# MCU.net
KiCad netlist of a schematic drawn in Altium Designer
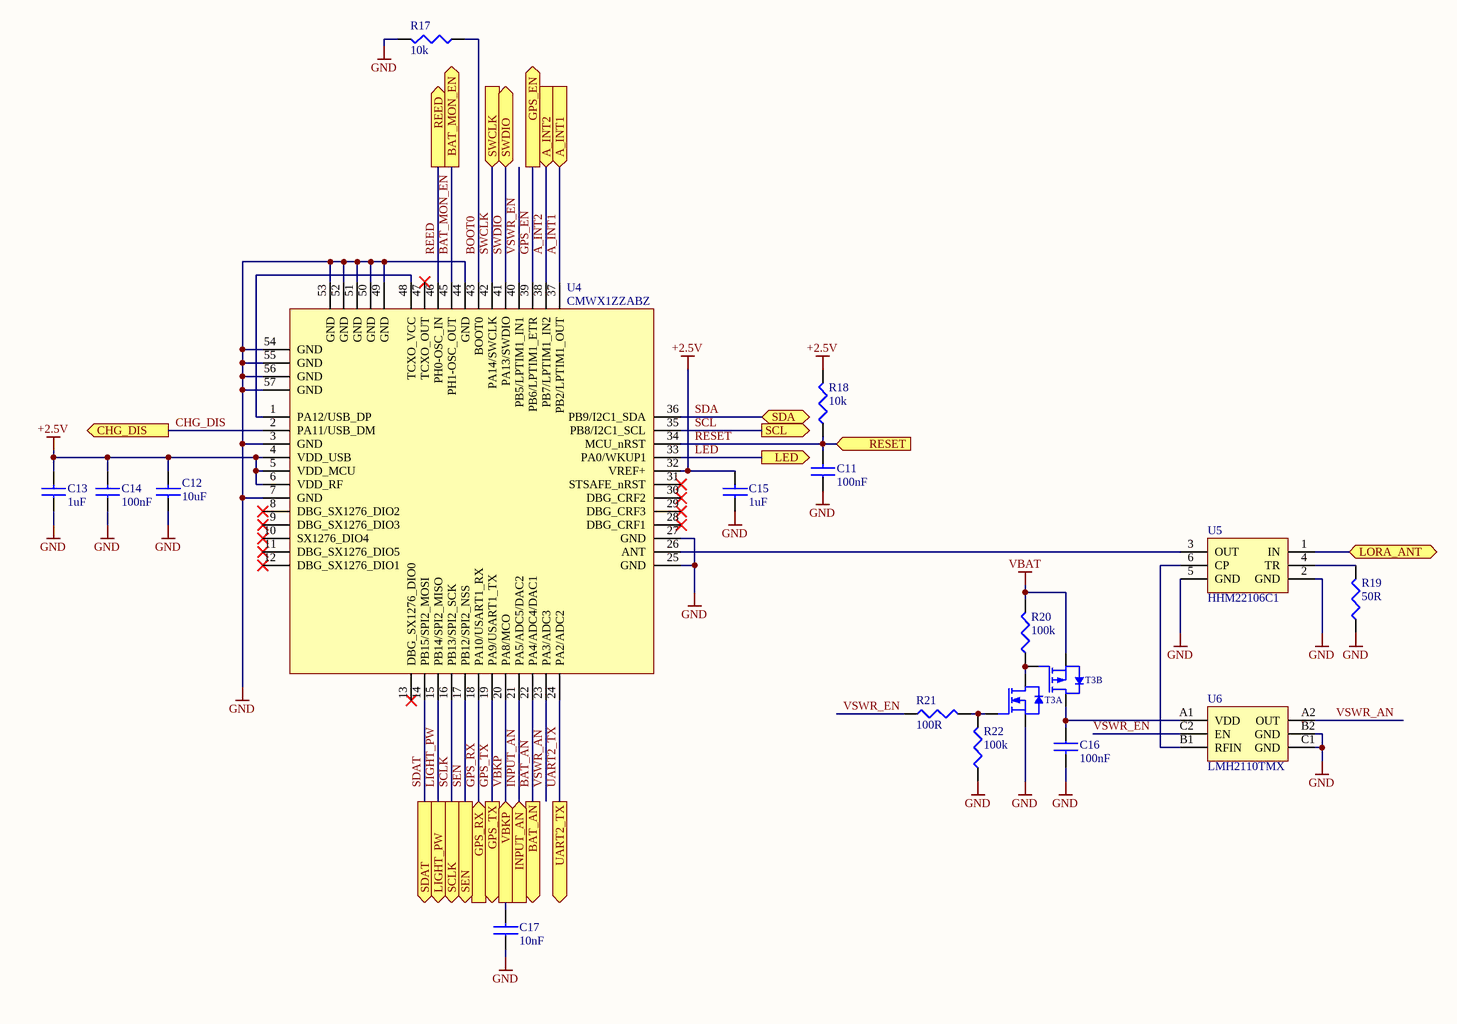
[diagram p0: MCU.SchDoc]

(export (version "E")
  (design (tool "Eeschema 10.0.6"))
  (components
    (comp (ref "C11")
      (value "100nF")
      (footprint "CAP0402")
      (fields
        (field (name "MANUFACTURER") "Multicomp")
        (field (name "MANUFACTURER PART NUMBER") "MC0402X104J160CT")
        (field (name "TOLERANCE") "5%")
      )
      (libsource (lib "Passive") (part "C - 100nF/0402"))
    )
    (comp (ref "C12")
      (value "10uF")
      (footprint "CAP0603")
      (description "10uf/0603/20%")
      (fields
        (field (name "MANUFACTURER") "KEMET")
        (field (name "MANUFACTURER PART NUMBER") "C0603C106M8PACTU")
      )
      (libsource (lib "pira-smart-schlib") (part "10uF"))
    )
    (comp (ref "C13")
      (value "1uF")
      (footprint "CAP0402")
      (description "CAP CER 1UF 10V 20% X5R 0402")
      (fields
        (field (name "MANUFACTURER") "Murata")
        (field (name "MANUFACTURER PART NUMBER") "GRM155R61A105ME15D")
      )
      (libsource (lib "Passive") (part "C - 1uF/0402"))
    )
    (comp (ref "C14")
      (value "100nF")
      (footprint "CAP0402")
      (fields
        (field (name "MANUFACTURER") "Multicomp")
        (field (name "MANUFACTURER PART NUMBER") "MC0402X104J160CT")
        (field (name "TOLERANCE") "5%")
      )
      (libsource (lib "Passive") (part "C - 100nF/0402"))
    )
    (comp (ref "C15")
      (value "1uF")
      (footprint "CAP0402")
      (description "CAP CER 1UF 10V 20% X5R 0402")
      (fields
        (field (name "MANUFACTURER") "Murata")
        (field (name "MANUFACTURER PART NUMBER") "GRM155R61A105ME15D")
      )
      (libsource (lib "Passive") (part "C - 1uF/0402"))
    )
    (comp (ref "C16")
      (value "100nF")
      (footprint "CAP0402")
      (fields
        (field (name "MANUFACTURER") "Multicomp")
        (field (name "MANUFACTURER PART NUMBER") "MC0402X104J160CT")
        (field (name "TOLERANCE") "5%")
      )
      (libsource (lib "Passive") (part "C - 100nF/0402"))
    )
    (comp (ref "C17")
      (value "10nF")
      (footprint "CAP0402")
      (description "CAP CER 10000PF 16V X7R 0402")
      (fields
        (field (name "MANUFACTURER") "Murata")
        (field (name "MANUFACTURER PART NUMBER") "GRM155R71C103KA01D")
      )
      (libsource (lib "Passive") (part "C - 10nF/0402"))
    )
    (comp (ref "R17")
      (value "10k")
      (footprint "RES0402")
      (fields
        (field (name "MANUFACTURER") "Multicomp")
        (field (name "MANUFACTURER PART NUMBER") "MCWR04X1002FTL")
        (field (name "TOLERANCE") "1%")
      )
      (libsource (lib "Passive") (part "R - 10k/0402"))
    )
    (comp (ref "R18")
      (value "10k")
      (footprint "RES0402")
      (fields
        (field (name "MANUFACTURER") "Multicomp")
        (field (name "MANUFACTURER PART NUMBER") "MCWR04X1002FTL")
        (field (name "TOLERANCE") "1%")
      )
      (libsource (lib "Passive") (part "R - 10k/0402"))
    )
    (comp (ref "R19")
      (value "50R")
      (footprint "RES0402")
      (description "SMD Chip Resistor, 0402 [1005 Metric], 50 ohm, FC Series, 30 V, Thin Film, 50 mW")
      (fields
        (field (name "MANUFACTURER") "Vishay")
        (field (name "MANUFACTURER PART NUMBER") "CRCW060351R0FKEA")
      )
      (libsource (lib "Passive") (part "R - 50R"))
    )
    (comp (ref "R20")
      (value "100k")
      (footprint "RES0402")
      (description "MULTICOMP   MCWR04X1003FTL   RES, THICK FILM, 100KOHM, 1%, 0.0625W")
      (fields
        (field (name "MANUFACTURER") "Multicomp")
        (field (name "MANUFACTURER PART NUMBER") "MCWR04X1003FTL")
      )
      (libsource (lib "Passive") (part "R - 100k/0402"))
    )
    (comp (ref "R21")
      (value "100R")
      (footprint "RES0402")
      (fields
        (field (name "MANUFACTURER") "Multicomp")
        (field (name "MANUFACTURER PART NUMBER") "MCMR04X1000FTL")
        (field (name "TOLERANCE") "1%")
      )
      (libsource (lib "Passive") (part "R - 100R/0402"))
    )
    (comp (ref "R22")
      (value "100k")
      (footprint "RES0402")
      (description "MULTICOMP   MCWR04X1003FTL   RES, THICK FILM, 100KOHM, 1%, 0.0625W")
      (fields
        (field (name "MANUFACTURER") "Multicomp")
        (field (name "MANUFACTURER PART NUMBER") "MCWR04X1003FTL")
      )
      (libsource (lib "Passive") (part "R - 100k/0402"))
    )
    (comp (ref "T3")
      (value "VT6M1T2CR")
      (footprint "VMT6")
      (description "Dual MOSFET, N and P Channel, 100 mA, 20 V, 2.5 ohm, 4.5 V, 1 V")
      (fields (field (name "AUTHOR") "Ciril Golob"))
      (libsource (lib "Active") (part "T_M - VT6M1T2CR"))
    )
    (comp (ref "U4")
      (value "CMWX1ZZABZ")
      (footprint "Lora Module ES0")
      (description "RF Module, FSK, OOK, LoRa, 4.8Kbps, 915MHz, -135.5dBm, 2.2V to 3.6V, I2C, SPI, UART, USB")
      (fields
        (field (name "MANUFACTURER") "Murata")
        (field (name "MANUFACTURER PART NUMBER") "CMWX1ZZABZ-091")
      )
      (libsource (lib "Active") (part "MCU - CMWX1ZZABZ"))
    )
    (comp (ref "U5")
      (value "HHM22106C1")
      (footprint "HHM22106C1")
      (description "Signal Conditioning DIRECTIONAL COUPLER 700-2700MHz")
      (fields (field (name "MANUFACTURER") "u-blox") (field (name "MANUFACTURER PART NUMBER") "MAX-M8Q-0"))
      (libsource (lib "Active") (part "RF - HHM22106C1"))
    )
    (comp (ref "U6")
      (value "LMH2110TMX")
      (footprint "DSBGA-6")
      (description "RF Detector IC GSM, EDGE, CDMA 50MHz ~ 8GHz -40dBm ~ 5dBm ±0,5dB")
      (fields (field (name "MANUFACTURER") "u-blox") (field (name "MANUFACTURER PART NUMBER") "MAX-M8Q-0"))
      (libsource (lib "Active") (part "RF - LMH2110TMX"))
    )
  )
  (nets
    (net (code "1") (name "+2.5V") (class "Default")
      (node (ref "C12") (pin "2") (pinfunction "2_2") (pintype "passive"))
      (node (ref "C13") (pin "2") (pinfunction "2_2") (pintype "passive"))
      (node (ref "C14") (pin "2") (pinfunction "2_2") (pintype "passive"))
      (node (ref "C15") (pin "2") (pinfunction "2_2") (pintype "passive"))
      (node (ref "R18") (pin "2") (pinfunction "2_2") (pintype "passive"))
      (node (ref "U4") (pin "32") (pinfunction "VREF+_32") (pintype "passive"))
      (node (ref "U4") (pin "4") (pinfunction "VDD_USB_4") (pintype "passive"))
      (node (ref "U4") (pin "5") (pinfunction "VDD_MCU_5") (pintype "passive"))
      (node (ref "U4") (pin "6") (pinfunction "VDD_RF_6") (pintype "passive"))
    )
    (net (code "2") (name "/A_INT1") (class "Default")
      (node (ref "U4") (pin "37") (pinfunction "PB2/LPTIM1_OUT_37") (pintype "passive"))
    )
    (net (code "3") (name "/A_INT2") (class "Default")
      (node (ref "U4") (pin "38") (pinfunction "PB7/LPTIM1_IN2_38") (pintype "passive"))
    )
    (net (code "4") (name "/BAT_AN") (class "Default")
      (node (ref "U4") (pin "22") (pinfunction "PA4/ADC4/DAC1_22") (pintype "passive"))
    )
    (net (code "5") (name "/BAT_MON_EN") (class "Default")
      (node (ref "U4") (pin "45") (pinfunction "PH1-OSC_OUT_45") (pintype "passive"))
    )
    (net (code "6") (name "/BOOT0") (class "Default")
      (node (ref "R17") (pin "1") (pinfunction "1_1") (pintype "passive"))
      (node (ref "U4") (pin "43") (pinfunction "BOOT0_43") (pintype "passive"))
    )
    (net (code "7") (name "/CHG_DIS") (class "Default")
      (node (ref "U4") (pin "2") (pinfunction "PA11/USB_DM_2") (pintype "passive"))
    )
    (net (code "8") (name "/GPS_EN") (class "Default")
      (node (ref "U4") (pin "39") (pinfunction "PB6/LPTIM1_ETR_39") (pintype "passive"))
    )
    (net (code "9") (name "/GPS_RX") (class "Default")
      (node (ref "U4") (pin "18") (pinfunction "PA10/USART1_RX_18") (pintype "passive"))
    )
    (net (code "10") (name "/GPS_TX") (class "Default")
      (node (ref "U4") (pin "19") (pinfunction "PA9/USART1_TX_19") (pintype "passive"))
    )
    (net (code "11") (name "/INPUT_AN") (class "Default")
      (node (ref "U4") (pin "21") (pinfunction "PA5/ADC5/DAC2_21") (pintype "passive"))
    )
    (net (code "12") (name "/LED") (class "Default")
      (node (ref "U4") (pin "33") (pinfunction "PA0/WKUP1_33") (pintype "passive"))
    )
    (net (code "13") (name "/LIGHT_PW") (class "Default")
      (node (ref "U4") (pin "15") (pinfunction "PB14/SPI2_MISO_15") (pintype "passive"))
    )
    (net (code "14") (name "/LORA_ANT") (class "Default")
      (node (ref "U5") (pin "1") (pinfunction "IN_1") (pintype "passive"))
    )
    (net (code "15") (name "/REED") (class "Default")
      (node (ref "U4") (pin "46") (pinfunction "PH0-OSC_IN_46") (pintype "passive"))
    )
    (net (code "16") (name "/RESET") (class "Default")
      (node (ref "C11") (pin "2") (pinfunction "2_2") (pintype "passive"))
      (node (ref "R18") (pin "1") (pinfunction "1_1") (pintype "passive"))
      (node (ref "U4") (pin "34") (pinfunction "MCU_nRST_34") (pintype "passive"))
    )
    (net (code "17") (name "/SCL") (class "Default")
      (node (ref "U4") (pin "35") (pinfunction "PB8/I2C1_SCL_35") (pintype "passive"))
    )
    (net (code "18") (name "/SCLK") (class "Default")
      (node (ref "U4") (pin "16") (pinfunction "PB13/SPI2_SCK_16") (pintype "passive"))
    )
    (net (code "19") (name "/SDA") (class "Default")
      (node (ref "U4") (pin "36") (pinfunction "PB9/I2C1_SDA_36") (pintype "passive"))
    )
    (net (code "20") (name "/SDAT") (class "Default")
      (node (ref "U4") (pin "14") (pinfunction "PB15/SPI2_MOSI_14") (pintype "passive"))
    )
    (net (code "21") (name "/SEN") (class "Default")
      (node (ref "U4") (pin "17") (pinfunction "PB12/SPI2_NSS_17") (pintype "passive"))
    )
    (net (code "22") (name "/SWCLK") (class "Default")
      (node (ref "U4") (pin "42") (pinfunction "PA14/SWCLK_42") (pintype "passive"))
    )
    (net (code "23") (name "/SWDIO") (class "Default")
      (node (ref "U4") (pin "41") (pinfunction "PA13/SWDIO_41") (pintype "passive"))
    )
    (net (code "24") (name "/UART2_TX") (class "Default")
      (node (ref "U4") (pin "24") (pinfunction "PA2/ADC2_24") (pintype "passive"))
    )
    (net (code "25") (name "/VBKP") (class "Default")
      (node (ref "C17") (pin "2") (pinfunction "2_2") (pintype "passive"))
      (node (ref "U4") (pin "20") (pinfunction "PA8/MCO_20") (pintype "passive"))
    )
    (net (code "26") (name "/VSWR_AN") (class "Default")
      (node (ref "U4") (pin "23") (pinfunction "PA3/ADC3_23") (pintype "passive"))
      (node (ref "U6") (pin "A2") (pinfunction "OUT_A2") (pintype "passive"))
    )
    (net (code "27") (name "/VSWR_EN") (class "Default")
      (node (ref "R21") (pin "1") (pinfunction "1_1") (pintype "passive"))
      (node (ref "U4") (pin "40") (pinfunction "PB5/LPTIM1_IN1_40") (pintype "passive"))
      (node (ref "U6") (pin "C2") (pinfunction "EN_C2") (pintype "passive"))
    )
    (net (code "28") (name "GND") (class "Default")
      (node (ref "C11") (pin "1") (pinfunction "1_1") (pintype "passive"))
      (node (ref "C12") (pin "1") (pinfunction "1_1") (pintype "passive"))
      (node (ref "C13") (pin "1") (pinfunction "1_1") (pintype "passive"))
      (node (ref "C14") (pin "1") (pinfunction "1_1") (pintype "passive"))
      (node (ref "C15") (pin "1") (pinfunction "1_1") (pintype "passive"))
      (node (ref "C16") (pin "2") (pinfunction "2_2") (pintype "passive"))
      (node (ref "C17") (pin "1") (pinfunction "1_1") (pintype "passive"))
      (node (ref "R17") (pin "2") (pinfunction "2_2") (pintype "passive"))
      (node (ref "R19") (pin "1") (pinfunction "1_1") (pintype "passive"))
      (node (ref "R22") (pin "1") (pinfunction "1_1") (pintype "passive"))
      (node (ref "T3") (pin "1") (pinfunction "S1_1") (pintype "passive"))
      (node (ref "U4") (pin "25") (pinfunction "GND_25") (pintype "passive"))
      (node (ref "U4") (pin "27") (pinfunction "GND_27") (pintype "passive"))
      (node (ref "U4") (pin "3") (pinfunction "GND_3") (pintype "passive"))
      (node (ref "U4") (pin "44") (pinfunction "GND_44") (pintype "passive"))
      (node (ref "U4") (pin "49") (pinfunction "GND_49") (pintype "passive"))
      (node (ref "U4") (pin "50") (pinfunction "GND_50") (pintype "passive"))
      (node (ref "U4") (pin "51") (pinfunction "GND_51") (pintype "passive"))
      (node (ref "U4") (pin "52") (pinfunction "GND_52") (pintype "passive"))
      (node (ref "U4") (pin "53") (pinfunction "GND_53") (pintype "passive"))
      (node (ref "U4") (pin "54") (pinfunction "GND_54") (pintype "passive"))
      (node (ref "U4") (pin "55") (pinfunction "GND_55") (pintype "passive"))
      (node (ref "U4") (pin "56") (pinfunction "GND_56") (pintype "passive"))
      (node (ref "U4") (pin "57") (pinfunction "GND_57") (pintype "passive"))
      (node (ref "U4") (pin "7") (pinfunction "GND_7") (pintype "passive"))
      (node (ref "U5") (pin "2") (pinfunction "GND_2") (pintype "passive"))
      (node (ref "U5") (pin "5") (pinfunction "GND_5") (pintype "passive"))
      (node (ref "U6") (pin "B2") (pinfunction "GND_B2") (pintype "passive"))
      (node (ref "U6") (pin "C1") (pinfunction "GND_C1") (pintype "passive"))
    )
    (net (code "29") (name "Net-(T3A-D1)") (class "Default")
      (node (ref "R20") (pin "1") (pinfunction "1_1") (pintype "passive"))
      (node (ref "T3") (pin "5") (pinfunction "G2_5") (pintype "passive"))
      (node (ref "T3") (pin "6") (pinfunction "D1_6") (pintype "passive"))
    )
    (net (code "30") (name "Net-(T3A-G1)") (class "Default")
      (node (ref "R21") (pin "2") (pinfunction "2_2") (pintype "passive"))
      (node (ref "R22") (pin "2") (pinfunction "2_2") (pintype "passive"))
      (node (ref "T3") (pin "2") (pinfunction "G1_2") (pintype "passive"))
    )
    (net (code "31") (name "Net-(T3B-D2)") (class "Default")
      (node (ref "C16") (pin "1") (pinfunction "1_1") (pintype "passive"))
      (node (ref "T3") (pin "3") (pinfunction "D2_3") (pintype "passive"))
      (node (ref "U6") (pin "A1") (pinfunction "VDD_A1") (pintype "passive"))
    )
    (net (code "32") (name "Net-(U4-ANT)") (class "Default")
      (node (ref "U4") (pin "26") (pinfunction "ANT_26") (pintype "passive"))
      (node (ref "U5") (pin "3") (pinfunction "OUT_3") (pintype "passive"))
    )
    (net (code "33") (name "Net-(U4-PA12{slash}USB_DP)") (class "Default")
      (node (ref "U4") (pin "1") (pinfunction "PA12/USB_DP_1") (pintype "passive"))
      (node (ref "U4") (pin "48") (pinfunction "TCXO_VCC_48") (pintype "passive"))
    )
    (net (code "34") (name "Net-(U5-CP)") (class "Default")
      (node (ref "U5") (pin "6") (pinfunction "CP_6") (pintype "passive"))
      (node (ref "U6") (pin "B1") (pinfunction "RFIN_B1") (pintype "passive"))
    )
    (net (code "35") (name "Net-(U5-TR)") (class "Default")
      (node (ref "R19") (pin "2") (pinfunction "2_2") (pintype "passive"))
      (node (ref "U5") (pin "4") (pinfunction "TR_4") (pintype "passive"))
    )
    (net (code "36") (name "VBAT") (class "Default")
      (node (ref "R20") (pin "2") (pinfunction "2_2") (pintype "passive"))
      (node (ref "T3") (pin "4") (pinfunction "S2_4") (pintype "passive"))
    )
    (net (code "37") (name "unconnected-(U4-DBG_CRF1-Pad28)") (class "Default")
      (node (ref "U4") (pin "28") (pinfunction "DBG_CRF1_28") (pintype "passive+no_connect"))
    )
    (net (code "38") (name "unconnected-(U4-DBG_CRF2-Pad30)") (class "Default")
      (node (ref "U4") (pin "30") (pinfunction "DBG_CRF2_30") (pintype "passive+no_connect"))
    )
    (net (code "39") (name "unconnected-(U4-DBG_CRF3-Pad29)") (class "Default")
      (node (ref "U4") (pin "29") (pinfunction "DBG_CRF3_29") (pintype "passive+no_connect"))
    )
    (net (code "40") (name "unconnected-(U4-DBG_SX1276_DIO0-Pad13)") (class "Default")
      (node (ref "U4") (pin "13") (pinfunction "DBG_SX1276_DIO0_13") (pintype "passive+no_connect"))
    )
    (net (code "41") (name "unconnected-(U4-DBG_SX1276_DIO1-Pad12)") (class "Default")
      (node (ref "U4") (pin "12") (pinfunction "DBG_SX1276_DIO1_12") (pintype "passive+no_connect"))
    )
    (net (code "42") (name "unconnected-(U4-DBG_SX1276_DIO2-Pad8)") (class "Default")
      (node (ref "U4") (pin "8") (pinfunction "DBG_SX1276_DIO2_8") (pintype "passive+no_connect"))
    )
    (net (code "43") (name "unconnected-(U4-DBG_SX1276_DIO3-Pad9)") (class "Default")
      (node (ref "U4") (pin "9") (pinfunction "DBG_SX1276_DIO3_9") (pintype "passive+no_connect"))
    )
    (net (code "44") (name "unconnected-(U4-DBG_SX1276_DIO5-Pad11)") (class "Default")
      (node (ref "U4") (pin "11") (pinfunction "DBG_SX1276_DIO5_11") (pintype "passive+no_connect"))
    )
    (net (code "45") (name "unconnected-(U4-STSAFE_nRST-Pad31)") (class "Default")
      (node (ref "U4") (pin "31") (pinfunction "STSAFE_nRST_31") (pintype "passive+no_connect"))
    )
    (net (code "46") (name "unconnected-(U4-SX1276_DIO4-Pad10)") (class "Default")
      (node (ref "U4") (pin "10") (pinfunction "SX1276_DIO4_10") (pintype "passive+no_connect"))
    )
    (net (code "47") (name "unconnected-(U4-TCXO_OUT-Pad47)") (class "Default")
      (node (ref "U4") (pin "47") (pinfunction "TCXO_OUT_47") (pintype "passive+no_connect"))
    )
  )
)
